# ping_imu_nano_v2.net
KiCad netlist of a schematic drawn in EAGLE
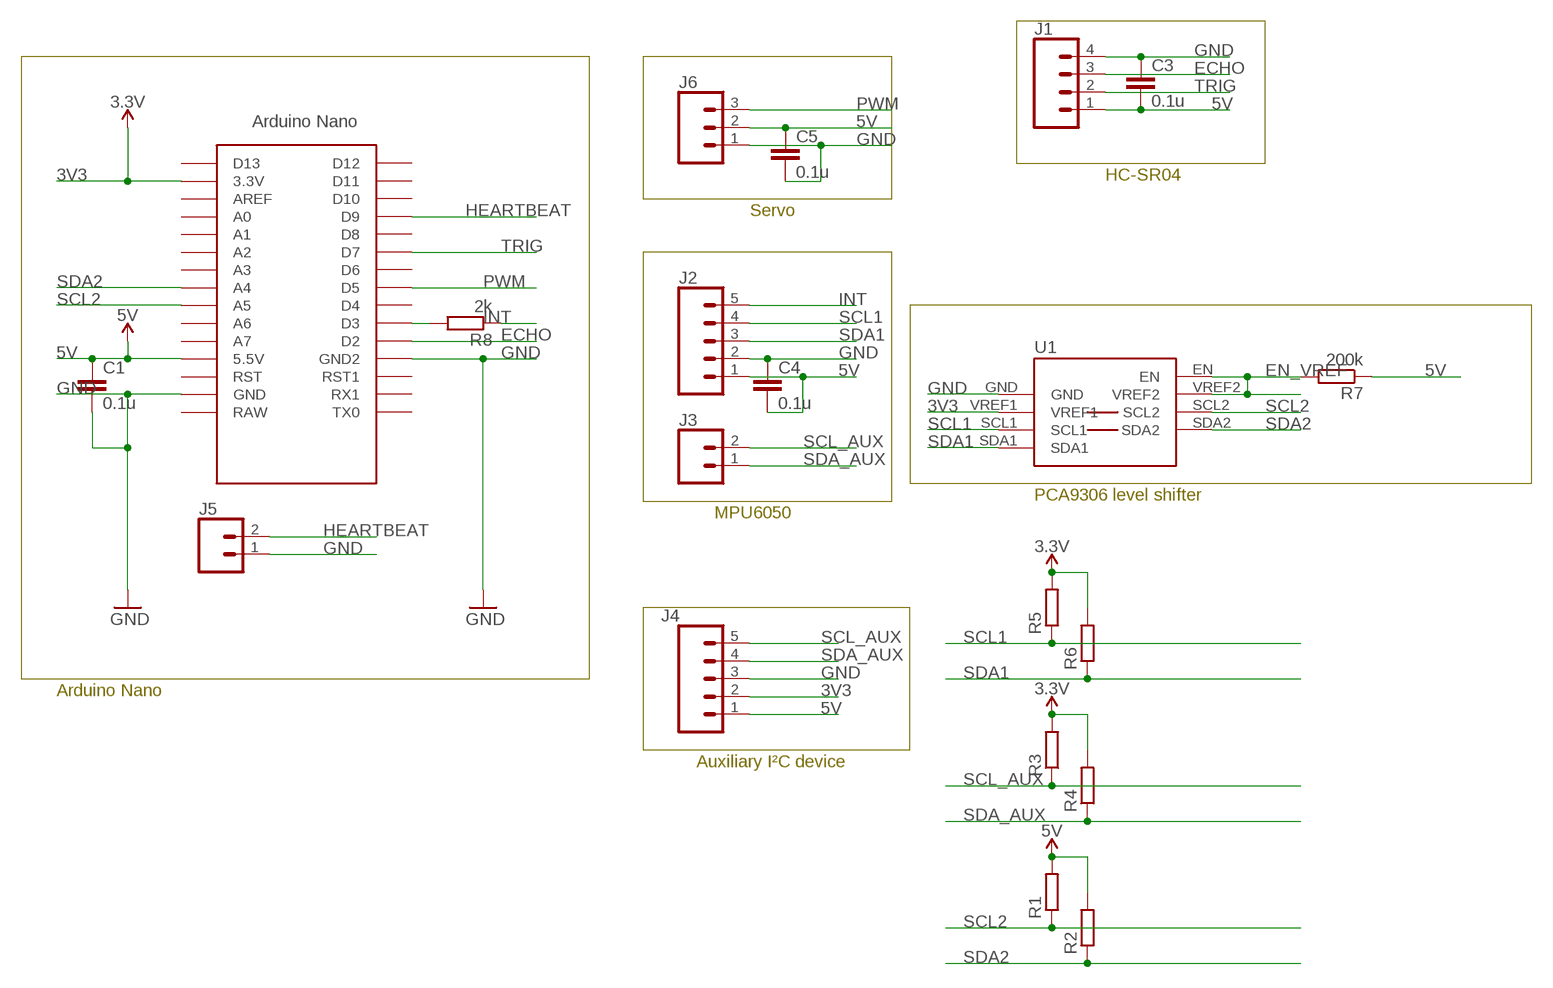
[diagram p0: schematic, sheet 1]

(export (version "E")
  (design (tool "Eeschema 10.0.6"))
  (components
    (comp (ref "C1")
      (value "0.1u")
      (footprint "eagle-import:C1206")
      (libsource (lib "eagle-import") (part "C-EUC1206"))
    )
    (comp (ref "C3")
      (value "0.1u")
      (footprint "eagle-import:C1206")
      (libsource (lib "eagle-import") (part "C-EUC1206"))
    )
    (comp (ref "C4")
      (value "0.1u")
      (footprint "eagle-import:C1206")
      (libsource (lib "eagle-import") (part "C-EUC1206"))
    )
    (comp (ref "C5")
      (value "0.1u")
      (footprint "eagle-import:C1206")
      (libsource (lib "eagle-import") (part "C-EUC1206"))
    )
    (comp (ref "J1")
      (value "CONN_04LONGPADS")
      (footprint "eagle-import:1X04_LONGPADS")
      (libsource (lib "eagle-import") (part "CONN_04LONGPADS"))
    )
    (comp (ref "J2")
      (value "CONN_05PTH_LONGPADS")
      (footprint "eagle-import:1X05_LONGPADS")
      (libsource (lib "eagle-import") (part "CONN_05PTH_LONGPADS"))
    )
    (comp (ref "J3")
      (value "CONN_02PTH3")
      (footprint "eagle-import:1X02_LONGPADS")
      (libsource (lib "eagle-import") (part "CONN_02PTH3"))
    )
    (comp (ref "J4")
      (value "CONN_05PTH_LONGPADS")
      (footprint "eagle-import:1X05_LONGPADS")
      (libsource (lib "eagle-import") (part "CONN_05PTH_LONGPADS"))
    )
    (comp (ref "J5")
      (value "CONN_02PTH3")
      (footprint "eagle-import:1X02_LONGPADS")
      (libsource (lib "eagle-import") (part "CONN_02PTH3"))
    )
    (comp (ref "J6")
      (value "CONN_03LONGPADS")
      (footprint "eagle-import:1X03_LONGPADS")
      (libsource (lib "eagle-import") (part "CONN_03LONGPADS"))
    )
    (comp (ref "R1")
      (value "R-EU_M1206")
      (footprint "eagle-import:M1206")
      (libsource (lib "eagle-import") (part "R-EU_M1206"))
    )
    (comp (ref "R2")
      (value "R-EU_M1206")
      (footprint "eagle-import:M1206")
      (libsource (lib "eagle-import") (part "R-EU_M1206"))
    )
    (comp (ref "R3")
      (value "R-EU_M1206")
      (footprint "eagle-import:M1206")
      (libsource (lib "eagle-import") (part "R-EU_M1206"))
    )
    (comp (ref "R4")
      (value "R-EU_M1206")
      (footprint "eagle-import:M1206")
      (libsource (lib "eagle-import") (part "R-EU_M1206"))
    )
    (comp (ref "R5")
      (value "R-EU_M1206")
      (footprint "eagle-import:M1206")
      (libsource (lib "eagle-import") (part "R-EU_M1206"))
    )
    (comp (ref "R6")
      (value "R-EU_M1206")
      (footprint "eagle-import:M1206")
      (libsource (lib "eagle-import") (part "R-EU_M1206"))
    )
    (comp (ref "R7")
      (value "200k")
      (footprint "eagle-import:M1206")
      (libsource (lib "eagle-import") (part "R-EU_M1206"))
    )
    (comp (ref "R8")
      (value "2k")
      (footprint "eagle-import:M1206")
      (libsource (lib "eagle-import") (part "R-EU_M1206"))
    )
    (comp (ref "U$1")
      (value "NANO_BARE")
      (footprint "eagle-import:NANO_BARE")
      (libsource (lib "eagle-import") (part "NANO_BARE"))
    )
    (comp (ref "U1")
      (value "PCA9306SO8")
      (footprint "eagle-import:SO8")
      (libsource (lib "eagle-import") (part "PCA9306SO8"))
    )
  )
  (nets
    (net (code "1") (name "/ECHO") (class "Default")
      (node (ref "J1") (pin "3") (pinfunction "3_3") (pintype "passive"))
      (node (ref "U$1") (pin "D2") (pinfunction "D2_D2") (pintype "bidirectional"))
    )
    (net (code "2") (name "/EN_VREF") (class "Default")
      (node (ref "R7") (pin "2") (pinfunction "2_2") (pintype "passive"))
      (node (ref "U1") (pin "EN") (pinfunction "EN_EN") (pintype "bidirectional"))
      (node (ref "U1") (pin "VREF2") (pinfunction "VREF2_VREF2") (pintype "bidirectional"))
    )
    (net (code "3") (name "/HEARTBEAT") (class "Default")
      (node (ref "J5") (pin "2") (pinfunction "2_2") (pintype "passive"))
      (node (ref "U$1") (pin "D9") (pinfunction "D9_D9") (pintype "bidirectional"))
    )
    (net (code "4") (name "/INT") (class "Default")
      (node (ref "J2") (pin "5") (pinfunction "5_5") (pintype "passive"))
      (node (ref "R8") (pin "1") (pinfunction "1_1") (pintype "passive"))
    )
    (net (code "5") (name "/PWM") (class "Default")
      (node (ref "J6") (pin "3") (pinfunction "3_3") (pintype "passive"))
      (node (ref "U$1") (pin "D5") (pinfunction "D5_D5") (pintype "bidirectional"))
    )
    (net (code "6") (name "/SCL1") (class "Default")
      (node (ref "J2") (pin "4") (pinfunction "4_4") (pintype "passive"))
      (node (ref "R5") (pin "1") (pinfunction "1_1") (pintype "passive"))
      (node (ref "U1") (pin "SCL1") (pinfunction "SCL1_SCL1") (pintype "bidirectional"))
    )
    (net (code "7") (name "/SCL2") (class "Default")
      (node (ref "R1") (pin "1") (pinfunction "1_1") (pintype "passive"))
      (node (ref "U$1") (pin "A5") (pinfunction "A5_A5") (pintype "bidirectional"))
      (node (ref "U1") (pin "SCL2") (pinfunction "SCL2_SCL2") (pintype "bidirectional"))
    )
    (net (code "8") (name "/SCL_AUX") (class "Default")
      (node (ref "J3") (pin "2") (pinfunction "2_2") (pintype "passive"))
      (node (ref "J4") (pin "5") (pinfunction "5_5") (pintype "passive"))
      (node (ref "R3") (pin "1") (pinfunction "1_1") (pintype "passive"))
    )
    (net (code "9") (name "/SDA1") (class "Default")
      (node (ref "J2") (pin "3") (pinfunction "3_3") (pintype "passive"))
      (node (ref "R6") (pin "1") (pinfunction "1_1") (pintype "passive"))
      (node (ref "U1") (pin "SDA1") (pinfunction "SDA1_SDA1") (pintype "bidirectional"))
    )
    (net (code "10") (name "/SDA2") (class "Default")
      (node (ref "R2") (pin "1") (pinfunction "1_1") (pintype "passive"))
      (node (ref "U$1") (pin "A4") (pinfunction "A4_A4") (pintype "bidirectional"))
      (node (ref "U1") (pin "SDA2") (pinfunction "SDA2_SDA2") (pintype "bidirectional"))
    )
    (net (code "11") (name "/SDA_AUX") (class "Default")
      (node (ref "J3") (pin "1") (pinfunction "1_1") (pintype "passive"))
      (node (ref "J4") (pin "4") (pinfunction "4_4") (pintype "passive"))
      (node (ref "R4") (pin "1") (pinfunction "1_1") (pintype "passive"))
    )
    (net (code "12") (name "/TRIG") (class "Default")
      (node (ref "J1") (pin "2") (pinfunction "2_2") (pintype "passive"))
      (node (ref "U$1") (pin "D7") (pinfunction "D7_D7") (pintype "bidirectional"))
    )
    (net (code "13") (name "3.3V") (class "Default")
      (node (ref "J4") (pin "2") (pinfunction "2_2") (pintype "passive"))
      (node (ref "R3") (pin "2") (pinfunction "2_2") (pintype "passive"))
      (node (ref "R4") (pin "2") (pinfunction "2_2") (pintype "passive"))
      (node (ref "R5") (pin "2") (pinfunction "2_2") (pintype "passive"))
      (node (ref "R6") (pin "2") (pinfunction "2_2") (pintype "passive"))
      (node (ref "U$1") (pin "3.3V") (pinfunction "3.3V_3.3V") (pintype "bidirectional"))
      (node (ref "U1") (pin "VREF1") (pinfunction "VREF1_VREF1") (pintype "bidirectional"))
    )
    (net (code "14") (name "5V") (class "Default")
      (node (ref "C1") (pin "1") (pinfunction "1_1") (pintype "passive"))
      (node (ref "C3") (pin "2") (pinfunction "2_2") (pintype "passive"))
      (node (ref "C4") (pin "2") (pinfunction "2_2") (pintype "passive"))
      (node (ref "C5") (pin "1") (pinfunction "1_1") (pintype "passive"))
      (node (ref "J1") (pin "1") (pinfunction "1_1") (pintype "passive"))
      (node (ref "J2") (pin "1") (pinfunction "1_1") (pintype "passive"))
      (node (ref "J4") (pin "1") (pinfunction "1_1") (pintype "passive"))
      (node (ref "J6") (pin "2") (pinfunction "2_2") (pintype "passive"))
      (node (ref "R1") (pin "2") (pinfunction "2_2") (pintype "passive"))
      (node (ref "R2") (pin "2") (pinfunction "2_2") (pintype "passive"))
      (node (ref "R7") (pin "1") (pinfunction "1_1") (pintype "passive"))
      (node (ref "U$1") (pin "5V") (pinfunction "5.5V_5V") (pintype "bidirectional"))
    )
    (net (code "15") (name "GND") (class "Default")
      (node (ref "C1") (pin "2") (pinfunction "2_2") (pintype "passive"))
      (node (ref "C3") (pin "1") (pinfunction "1_1") (pintype "passive"))
      (node (ref "C4") (pin "1") (pinfunction "1_1") (pintype "passive"))
      (node (ref "C5") (pin "2") (pinfunction "2_2") (pintype "passive"))
      (node (ref "J1") (pin "4") (pinfunction "4_4") (pintype "passive"))
      (node (ref "J2") (pin "2") (pinfunction "2_2") (pintype "passive"))
      (node (ref "J4") (pin "3") (pinfunction "3_3") (pintype "passive"))
      (node (ref "J5") (pin "1") (pinfunction "1_1") (pintype "passive"))
      (node (ref "J6") (pin "1") (pinfunction "1_1") (pintype "passive"))
      (node (ref "U$1") (pin "GND") (pinfunction "GND_GND") (pintype "bidirectional"))
      (node (ref "U$1") (pin "GND1") (pinfunction "GND2_GND1") (pintype "bidirectional"))
      (node (ref "U1") (pin "GND") (pinfunction "GND_GND") (pintype "bidirectional"))
    )
    (net (code "16") (name "Net-(R8-Pad2)") (class "Default")
      (node (ref "R8") (pin "2") (pinfunction "2_2") (pintype "passive"))
      (node (ref "U$1") (pin "D3") (pinfunction "D3_D3") (pintype "bidirectional"))
    )
    (net (code "17") (name "unconnected-(U$1-PadA0)") (class "Default")
      (node (ref "U$1") (pin "A0") (pinfunction "A0_A0") (pintype "bidirectional"))
    )
    (net (code "18") (name "unconnected-(U$1-PadA1)") (class "Default")
      (node (ref "U$1") (pin "A1") (pinfunction "A1_A1") (pintype "bidirectional"))
    )
    (net (code "19") (name "unconnected-(U$1-PadA2)") (class "Default")
      (node (ref "U$1") (pin "A2") (pinfunction "A2_A2") (pintype "bidirectional"))
    )
    (net (code "20") (name "unconnected-(U$1-PadA3)") (class "Default")
      (node (ref "U$1") (pin "A3") (pinfunction "A3_A3") (pintype "bidirectional"))
    )
    (net (code "21") (name "unconnected-(U$1-PadA6)") (class "Default")
      (node (ref "U$1") (pin "A6") (pinfunction "A6_A6") (pintype "bidirectional"))
    )
    (net (code "22") (name "unconnected-(U$1-PadA7)") (class "Default")
      (node (ref "U$1") (pin "A7") (pinfunction "A7_A7") (pintype "bidirectional"))
    )
    (net (code "23") (name "unconnected-(U$1-PadAREF)") (class "Default")
      (node (ref "U$1") (pin "AREF") (pinfunction "AREF_AREF") (pintype "bidirectional"))
    )
    (net (code "24") (name "unconnected-(U$1-PadD4)") (class "Default")
      (node (ref "U$1") (pin "D4") (pinfunction "D4_D4") (pintype "bidirectional"))
    )
    (net (code "25") (name "unconnected-(U$1-PadD6)") (class "Default")
      (node (ref "U$1") (pin "D6") (pinfunction "D6_D6") (pintype "bidirectional"))
    )
    (net (code "26") (name "unconnected-(U$1-PadD8)") (class "Default")
      (node (ref "U$1") (pin "D8") (pinfunction "D8_D8") (pintype "bidirectional"))
    )
    (net (code "27") (name "unconnected-(U$1-PadD10)") (class "Default")
      (node (ref "U$1") (pin "D10") (pinfunction "D10_D10") (pintype "bidirectional"))
    )
    (net (code "28") (name "unconnected-(U$1-PadD11)") (class "Default")
      (node (ref "U$1") (pin "D11") (pinfunction "D11_D11") (pintype "bidirectional"))
    )
    (net (code "29") (name "unconnected-(U$1-PadD12)") (class "Default")
      (node (ref "U$1") (pin "D12") (pinfunction "D12_D12") (pintype "bidirectional"))
    )
    (net (code "30") (name "unconnected-(U$1-PadD13)") (class "Default")
      (node (ref "U$1") (pin "D13") (pinfunction "D13_D13") (pintype "bidirectional"))
    )
    (net (code "31") (name "unconnected-(U$1-PadRAW)") (class "Default")
      (node (ref "U$1") (pin "RAW") (pinfunction "RAW_RAW") (pintype "bidirectional"))
    )
    (net (code "32") (name "unconnected-(U$1-PadRST)") (class "Default")
      (node (ref "U$1") (pin "RST") (pinfunction "RST_RST") (pintype "bidirectional"))
    )
    (net (code "33") (name "unconnected-(U$1-PadRST1)") (class "Default")
      (node (ref "U$1") (pin "RST1") (pinfunction "RST1_RST1") (pintype "bidirectional"))
    )
    (net (code "34") (name "unconnected-(U$1-PadRX1)") (class "Default")
      (node (ref "U$1") (pin "RX1") (pinfunction "RX1_RX1") (pintype "bidirectional"))
    )
    (net (code "35") (name "unconnected-(U$1-PadTX0)") (class "Default")
      (node (ref "U$1") (pin "TX0") (pinfunction "TX0_TX0") (pintype "bidirectional"))
    )
  )
)
